# Sheet_20190224.net
KiCad netlist of a schematic drawn in Altium Designer
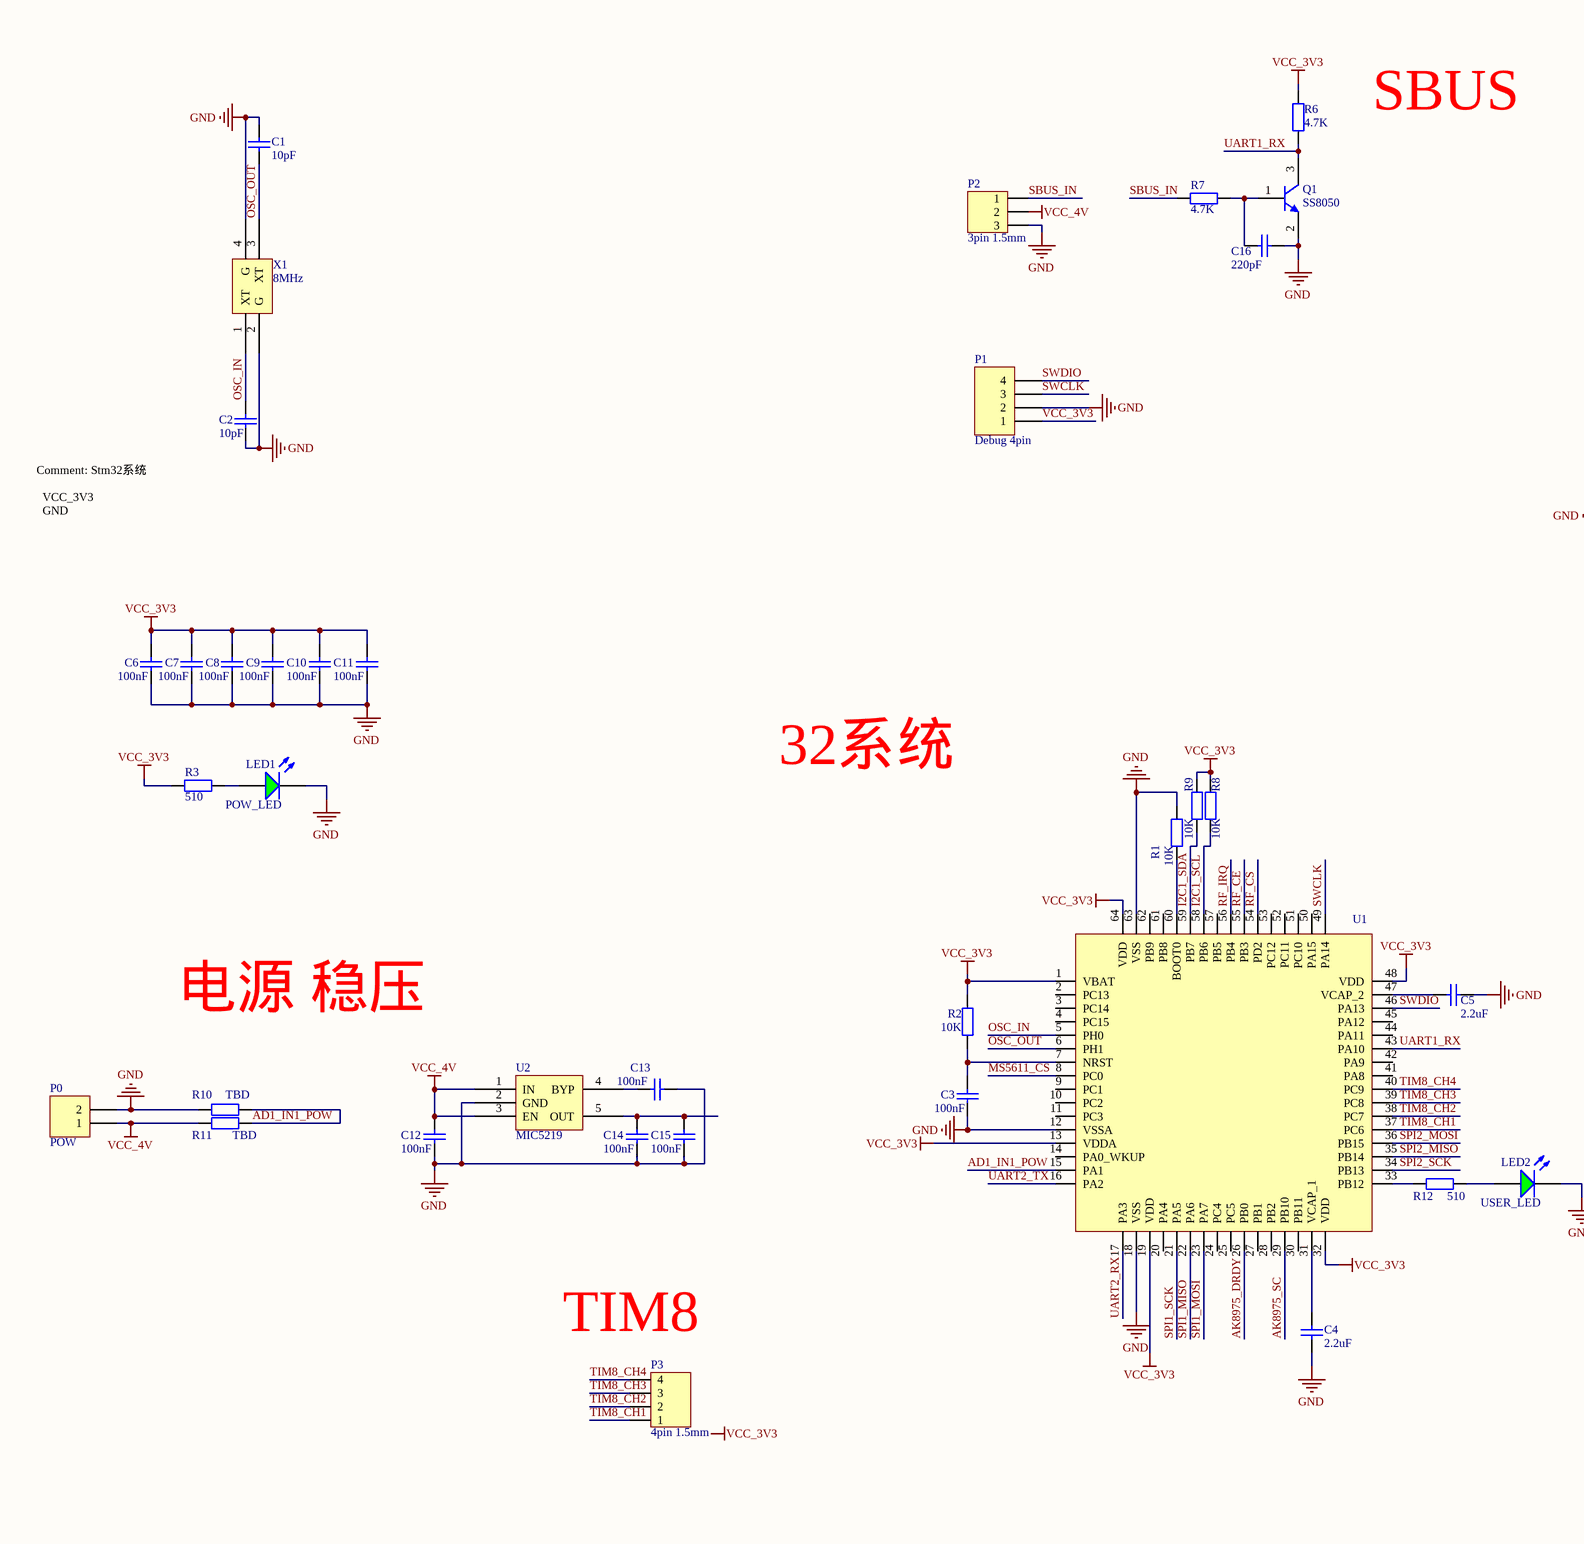
[diagram p0: Sheet_20190224.SchDoc, left]
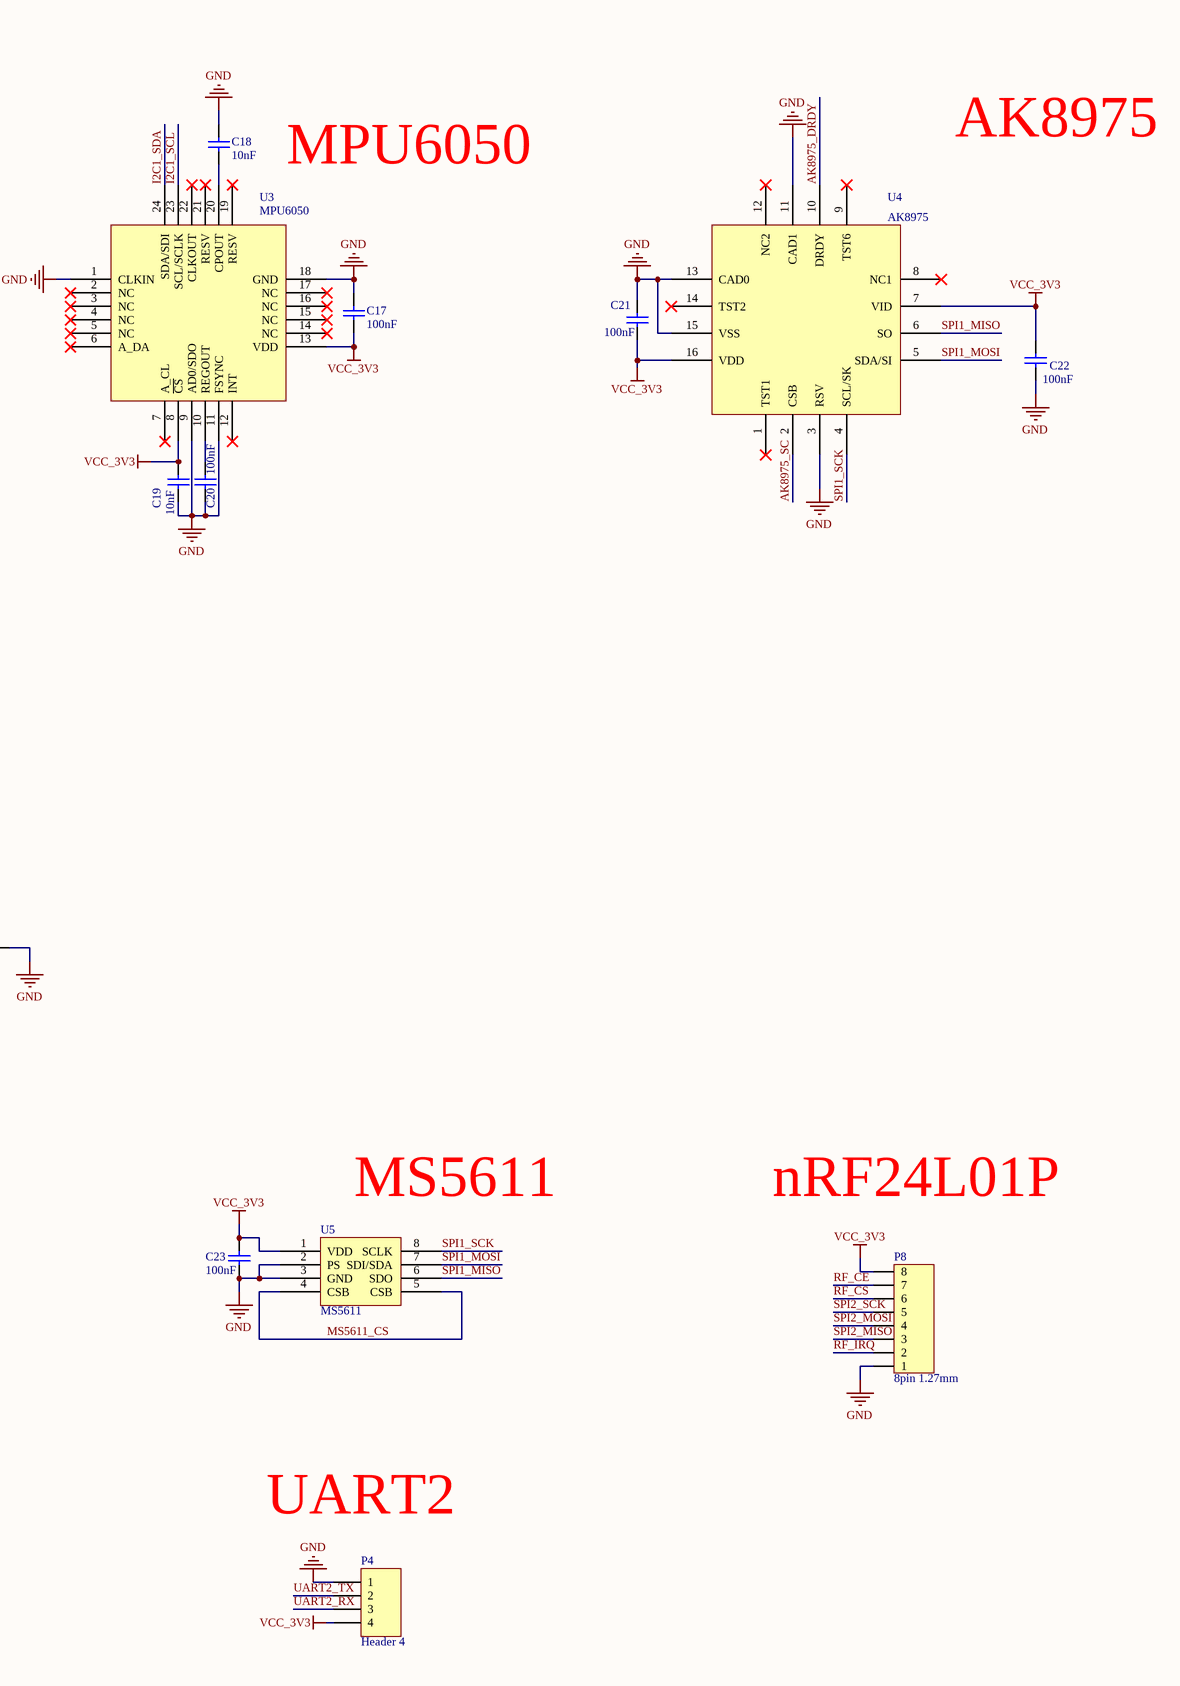
[diagram p1: Sheet_20190224.SchDoc, right]

(export (version "E")
  (design (tool "Eeschema 10.0.6"))
  (components
    (comp (ref "C1")
      (value "10pF")
      (footprint "0402 C")
      (libsource (lib "FlightController_Integrated_Library") (part "0402 C"))
    )
    (comp (ref "C2")
      (value "10pF")
      (footprint "0402 C")
      (libsource (lib "FlightController_Integrated_Library") (part "0402 C"))
    )
    (comp (ref "C3")
      (value "100nF")
      (footprint "0402 C")
      (libsource (lib "FlightController_Integrated_Library") (part "0402 C"))
    )
    (comp (ref "C4")
      (value "2.2uF")
      (footprint "0603 C")
      (libsource (lib "FlightController_Integrated_Library") (part "0603 C"))
    )
    (comp (ref "C5")
      (value "2.2uF")
      (footprint "0603 C")
      (libsource (lib "FlightController_Integrated_Library") (part "0603 C"))
    )
    (comp (ref "C6")
      (value "100nF")
      (footprint "0402 C")
      (libsource (lib "FlightController_Integrated_Library") (part "0402 C"))
    )
    (comp (ref "C7")
      (value "100nF")
      (footprint "0402 C")
      (libsource (lib "FlightController_Integrated_Library") (part "0402 C"))
    )
    (comp (ref "C8")
      (value "100nF")
      (footprint "0402 C")
      (libsource (lib "FlightController_Integrated_Library") (part "0402 C"))
    )
    (comp (ref "C9")
      (value "100nF")
      (footprint "0402 C")
      (libsource (lib "FlightController_Integrated_Library") (part "0402 C"))
    )
    (comp (ref "C10")
      (value "100nF")
      (footprint "0402 C")
      (libsource (lib "FlightController_Integrated_Library") (part "0402 C"))
    )
    (comp (ref "C11")
      (value "100nF")
      (footprint "0402 C")
      (libsource (lib "FlightController_Integrated_Library") (part "0402 C"))
    )
    (comp (ref "C12")
      (value "100nF")
      (footprint "0402 C")
      (libsource (lib "FlightController_Integrated_Library") (part "0402 C"))
    )
    (comp (ref "C13")
      (value "100nF")
      (footprint "0402 C")
      (libsource (lib "FlightController_Integrated_Library") (part "0402 C"))
    )
    (comp (ref "C14")
      (value "100nF")
      (footprint "0402 C")
      (libsource (lib "FlightController_Integrated_Library") (part "0402 C"))
    )
    (comp (ref "C15")
      (value "100nF")
      (footprint "0402 C")
      (libsource (lib "FlightController_Integrated_Library") (part "0402 C"))
    )
    (comp (ref "C16")
      (value "220pF")
      (footprint "0402 C")
      (libsource (lib "FlightController_Integrated_Library") (part "0402 C"))
    )
    (comp (ref "C17")
      (value "100nF")
      (footprint "0402 C")
      (libsource (lib "FlightController_Integrated_Library") (part "0402 C"))
    )
    (comp (ref "C18")
      (value "10nF")
      (footprint "0402 C")
      (libsource (lib "FlightController_Integrated_Library") (part "0402 C"))
    )
    (comp (ref "C19")
      (value "10nF")
      (footprint "0402 C")
      (libsource (lib "FlightController_Integrated_Library") (part "0402 C"))
    )
    (comp (ref "C20")
      (value "100nF")
      (footprint "0402 C")
      (libsource (lib "FlightController_Integrated_Library") (part "0402 C"))
    )
    (comp (ref "C21")
      (value "100nF")
      (footprint "0402 C")
      (libsource (lib "FlightController_Integrated_Library") (part "0402 C"))
    )
    (comp (ref "C22")
      (value "100nF")
      (footprint "0402 C")
      (libsource (lib "FlightController_Integrated_Library") (part "0402 C"))
    )
    (comp (ref "C23")
      (value "100nF")
      (footprint "0402 C")
      (libsource (lib "FlightController_Integrated_Library") (part "0402 C"))
    )
    (comp (ref "LED1")
      (value "POW_LED")
      (footprint "0603 LED")
      (libsource (lib "FlightController_Integrated_Library") (part "0603 LED"))
    )
    (comp (ref "LED2")
      (value "USER_LED")
      (footprint "0603 LED")
      (libsource (lib "FlightController_Integrated_Library") (part "0603 LED"))
    )
    (comp (ref "P0")
      (value "POW")
      (footprint "HDR1X2")
      (description "Header, 2-Pin")
      (fields (field (name "PUBLISHER") "Altium Limited"))
      (libsource (lib "Miscellaneous Connectors") (part "Header 2"))
    )
    (comp (ref "P1")
      (value "Debug 4pin")
      (footprint "GH-1.25 4pin")
      (libsource (lib "FlightController_Integrated_Library") (part "Debug 4pin"))
    )
    (comp (ref "P2")
      (value "3pin 1.5mm")
      (footprint "3pin 1.5mm")
      (libsource (lib "FlightController_Integrated_Library") (part "3pin 1.5mm"))
    )
    (comp (ref "P3")
      (value "4pin 1.5mm")
      (footprint "4pin 1.5mm")
      (libsource (lib "FlightController_Integrated_Library") (part "4pin 1.5mm"))
    )
    (comp (ref "P4")
      (value "Header 4")
      (footprint "HDR1X4")
      (description "Header, 4-Pin")
      (fields (field (name "PUBLISHER") "Altium Limited"))
      (libsource (lib "Miscellaneous Connectors") (part "Header 4"))
    )
    (comp (ref "P8")
      (value "8pin 1.27mm")
      (footprint "8pin 1.27mm")
      (libsource (lib "FlightController_Integrated_Library") (part "8pin 1.27mm"))
    )
    (comp (ref "Q1")
      (value "SS8050")
      (footprint "SOT-23 3pin")
      (libsource (lib "FlightController_Integrated_Library") (part "SS8050"))
    )
    (comp (ref "R1")
      (value "10K")
      (footprint "0402 R")
      (libsource (lib "FlightController_Integrated_Library") (part "0402 R"))
    )
    (comp (ref "R2")
      (value "10K")
      (footprint "0402 R")
      (libsource (lib "FlightController_Integrated_Library") (part "0402 R"))
    )
    (comp (ref "R3") (value "510") (footprint "0402 R") (libsource (lib "") (part "0402 R_3")))
    (comp (ref "R6") (value "4.7K") (footprint "0402 R") (libsource (lib "") (part "0402 R_2")))
    (comp (ref "R7") (value "4.7K") (footprint "0402 R") (libsource (lib "") (part "0402 R_3")))
    (comp (ref "R8") (value "10K") (footprint "0402 R") (libsource (lib "") (part "0402 R_2")))
    (comp (ref "R9") (value "10K") (footprint "0402 R") (libsource (lib "") (part "0402 R_2")))
    (comp (ref "R10") (value "TBD") (footprint "0402 R") (libsource (lib "") (part "0402 R_1")))
    (comp (ref "R11") (value "TBD") (footprint "0402 R") (libsource (lib "") (part "0402 R_1")))
    (comp (ref "R12") (value "510") (footprint "0402 R") (libsource (lib "") (part "0402 R_1")))
    (comp (ref "U1")
      (value "STM32F407VET6_64")
      (footprint "LQFP 64pin")
      (libsource (lib "FlightController_Integrated_Library") (part "STM32F407VET6_64"))
    )
    (comp (ref "U2")
      (value "MIC5219")
      (footprint "SOT-23 5pin")
      (libsource (lib "FlightController_Integrated_Library") (part "MIC5219"))
    )
    (comp (ref "U3")
      (value "MPU6050")
      (footprint "QFN 24pin")
      (libsource (lib "FlightController_Integrated_Library") (part "MPU6000/6050"))
    )
    (comp (ref "U4")
      (value "AK8975")
      (footprint "AK8975")
      (libsource (lib "FlightController_Integrated_Library") (part "AK8975"))
    )
    (comp (ref "U5")
      (value "MS5611")
      (footprint "MS5611")
      (libsource (lib "FlightController_Integrated_Library") (part "MS5611"))
    )
    (comp (ref "X1")
      (value "8MHz")
      (footprint "XTAL_3225 4pin")
      (libsource (lib "FlightController_Integrated_Library") (part "XTAL"))
    )
  )
  (nets
    (net (code "1") (name "/AD1_IN1_POW") (class "Default")
      (node (ref "R10") (pin "2") (pinfunction "2_2") (pintype "passive"))
      (node (ref "R11") (pin "2") (pinfunction "2_2") (pintype "passive"))
      (node (ref "U1") (pin "15") (pinfunction "PA1_15") (pintype "passive"))
    )
    (net (code "2") (name "/AK8975_DRDY") (class "Default")
      (node (ref "U1") (pin "26") (pinfunction "PB0_26") (pintype "passive"))
      (node (ref "U4") (pin "10") (pinfunction "DRDY_10") (pintype "passive"))
    )
    (net (code "3") (name "/AK8975_SC") (class "Default")
      (node (ref "U1") (pin "29") (pinfunction "PB10_29") (pintype "passive"))
      (node (ref "U4") (pin "2") (pinfunction "CSB_2") (pintype "passive"))
    )
    (net (code "4") (name "/I2C1_SCL") (class "Default")
      (node (ref "R8") (pin "2") (pinfunction "2_2") (pintype "passive"))
      (node (ref "U1") (pin "58") (pinfunction "PB6_58") (pintype "passive"))
      (node (ref "U3") (pin "23") (pinfunction "SCL/SCLK_23") (pintype "passive"))
    )
    (net (code "5") (name "/I2C1_SDA") (class "Default")
      (node (ref "R9") (pin "2") (pinfunction "2_2") (pintype "passive"))
      (node (ref "U1") (pin "59") (pinfunction "PB7_59") (pintype "passive"))
      (node (ref "U3") (pin "24") (pinfunction "SDA/SDI_24") (pintype "passive"))
    )
    (net (code "6") (name "/MS5611_CS") (class "Default")
      (node (ref "U1") (pin "8") (pinfunction "PC0_8") (pintype "passive"))
      (node (ref "U5") (pin "4") (pinfunction "CSB_4") (pintype "passive"))
      (node (ref "U5") (pin "5") (pinfunction "CSB_5") (pintype "passive"))
    )
    (net (code "7") (name "/OSC_IN") (class "Default")
      (node (ref "C2") (pin "2") (pinfunction "2_2") (pintype "passive"))
      (node (ref "U1") (pin "5") (pinfunction "PH0_5") (pintype "passive"))
      (node (ref "X1") (pin "1") (pinfunction "XT_1") (pintype "passive"))
    )
    (net (code "8") (name "/OSC_OUT") (class "Default")
      (node (ref "C1") (pin "1") (pinfunction "1_1") (pintype "passive"))
      (node (ref "U1") (pin "6") (pinfunction "PH1_6") (pintype "passive"))
      (node (ref "X1") (pin "3") (pinfunction "XT_3") (pintype "passive"))
    )
    (net (code "9") (name "/RF_CE") (class "Default")
      (node (ref "P8") (pin "7") (pinfunction "7_7") (pintype "passive"))
      (node (ref "U1") (pin "55") (pinfunction "PB3_55") (pintype "passive"))
    )
    (net (code "10") (name "/RF_CS") (class "Default")
      (node (ref "P8") (pin "6") (pinfunction "6_6") (pintype "passive"))
      (node (ref "U1") (pin "54") (pinfunction "PD2_54") (pintype "passive"))
    )
    (net (code "11") (name "/RF_IRQ") (class "Default")
      (node (ref "P8") (pin "2") (pinfunction "2_2") (pintype "passive"))
      (node (ref "U1") (pin "56") (pinfunction "PB4_56") (pintype "passive"))
    )
    (net (code "12") (name "/SBUS_IN") (class "Default")
      (node (ref "P2") (pin "1") (pinfunction "1_1") (pintype "passive"))
      (node (ref "R7") (pin "2") (pinfunction "2_2") (pintype "passive"))
    )
    (net (code "13") (name "/SPI1_MISO") (class "Default")
      (node (ref "U1") (pin "22") (pinfunction "PA6_22") (pintype "passive"))
      (node (ref "U4") (pin "6") (pinfunction "SO_6") (pintype "passive"))
      (node (ref "U5") (pin "6") (pinfunction "SDO_6") (pintype "passive"))
    )
    (net (code "14") (name "/SPI1_MOSI") (class "Default")
      (node (ref "U1") (pin "23") (pinfunction "PA7_23") (pintype "passive"))
      (node (ref "U4") (pin "5") (pinfunction "SDA/SI_5") (pintype "passive"))
      (node (ref "U5") (pin "7") (pinfunction "SDI/SDA_7") (pintype "passive"))
    )
    (net (code "15") (name "/SPI1_SCK") (class "Default")
      (node (ref "U1") (pin "21") (pinfunction "PA5_21") (pintype "passive"))
      (node (ref "U4") (pin "4") (pinfunction "SCL/SK_4") (pintype "passive"))
      (node (ref "U5") (pin "8") (pinfunction "SCLK_8") (pintype "passive"))
    )
    (net (code "16") (name "/SPI2_MISO") (class "Default")
      (node (ref "P8") (pin "3") (pinfunction "3_3") (pintype "passive"))
      (node (ref "U1") (pin "35") (pinfunction "PB14_35") (pintype "passive"))
    )
    (net (code "17") (name "/SPI2_MOSI") (class "Default")
      (node (ref "P8") (pin "4") (pinfunction "4_4") (pintype "passive"))
      (node (ref "U1") (pin "36") (pinfunction "PB15_36") (pintype "passive"))
    )
    (net (code "18") (name "/SPI2_SCK") (class "Default")
      (node (ref "P8") (pin "5") (pinfunction "5_5") (pintype "passive"))
      (node (ref "U1") (pin "34") (pinfunction "PB13_34") (pintype "passive"))
    )
    (net (code "19") (name "/SWCLK") (class "Default")
      (node (ref "P1") (pin "3") (pinfunction "3_3") (pintype "passive"))
      (node (ref "U1") (pin "49") (pinfunction "PA14_49") (pintype "passive"))
    )
    (net (code "20") (name "/SWDIO") (class "Default")
      (node (ref "P1") (pin "4") (pinfunction "4_4") (pintype "passive"))
      (node (ref "U1") (pin "46") (pinfunction "PA13_46") (pintype "passive"))
    )
    (net (code "21") (name "/TIM8_CH1") (class "Default")
      (node (ref "P3") (pin "1") (pinfunction "1_1") (pintype "passive"))
      (node (ref "U1") (pin "37") (pinfunction "PC6_37") (pintype "passive"))
    )
    (net (code "22") (name "/TIM8_CH2") (class "Default")
      (node (ref "P3") (pin "2") (pinfunction "2_2") (pintype "passive"))
      (node (ref "U1") (pin "38") (pinfunction "PC7_38") (pintype "passive"))
    )
    (net (code "23") (name "/TIM8_CH3") (class "Default")
      (node (ref "P3") (pin "3") (pinfunction "3_3") (pintype "passive"))
      (node (ref "U1") (pin "39") (pinfunction "PC8_39") (pintype "passive"))
    )
    (net (code "24") (name "/TIM8_CH4") (class "Default")
      (node (ref "P3") (pin "4") (pinfunction "4_4") (pintype "passive"))
      (node (ref "U1") (pin "40") (pinfunction "PC9_40") (pintype "passive"))
    )
    (net (code "25") (name "/UART1_RX") (class "Default")
      (node (ref "Q1") (pin "3") (pinfunction "C_3") (pintype "passive"))
      (node (ref "R6") (pin "2") (pinfunction "2_2") (pintype "passive"))
      (node (ref "U1") (pin "43") (pinfunction "PA10_43") (pintype "passive"))
    )
    (net (code "26") (name "/UART2_RX") (class "Default")
      (node (ref "P4") (pin "3") (pinfunction "3_3") (pintype "passive"))
      (node (ref "U1") (pin "17") (pinfunction "PA3_17") (pintype "passive"))
    )
    (net (code "27") (name "/UART2_TX") (class "Default")
      (node (ref "P4") (pin "2") (pinfunction "2_2") (pintype "passive"))
      (node (ref "U1") (pin "16") (pinfunction "PA2_16") (pintype "passive"))
    )
    (net (code "28") (name "GND") (class "Default")
      (node (ref "C1") (pin "2") (pinfunction "2_2") (pintype "passive"))
      (node (ref "C10") (pin "1") (pinfunction "1_1") (pintype "passive"))
      (node (ref "C11") (pin "1") (pinfunction "1_1") (pintype "passive"))
      (node (ref "C12") (pin "1") (pinfunction "1_1") (pintype "passive"))
      (node (ref "C13") (pin "1") (pinfunction "1_1") (pintype "passive"))
      (node (ref "C14") (pin "1") (pinfunction "1_1") (pintype "passive"))
      (node (ref "C15") (pin "1") (pinfunction "1_1") (pintype "passive"))
      (node (ref "C16") (pin "1") (pinfunction "1_1") (pintype "passive"))
      (node (ref "C17") (pin "1") (pinfunction "1_1") (pintype "passive"))
      (node (ref "C18") (pin "1") (pinfunction "1_1") (pintype "passive"))
      (node (ref "C19") (pin "2") (pinfunction "2_2") (pintype "passive"))
      (node (ref "C2") (pin "1") (pinfunction "1_1") (pintype "passive"))
      (node (ref "C20") (pin "2") (pinfunction "2_2") (pintype "passive"))
      (node (ref "C21") (pin "1") (pinfunction "1_1") (pintype "passive"))
      (node (ref "C22") (pin "2") (pinfunction "2_2") (pintype "passive"))
      (node (ref "C23") (pin "1") (pinfunction "1_1") (pintype "passive"))
      (node (ref "C3") (pin "1") (pinfunction "1_1") (pintype "passive"))
      (node (ref "C4") (pin "1") (pinfunction "1_1") (pintype "passive"))
      (node (ref "C5") (pin "1") (pinfunction "1_1") (pintype "passive"))
      (node (ref "C6") (pin "1") (pinfunction "1_1") (pintype "passive"))
      (node (ref "C7") (pin "1") (pinfunction "1_1") (pintype "passive"))
      (node (ref "C8") (pin "1") (pinfunction "1_1") (pintype "passive"))
      (node (ref "C9") (pin "1") (pinfunction "1_1") (pintype "passive"))
      (node (ref "LED1") (pin "K") (pinfunction "K_K") (pintype "passive"))
      (node (ref "LED2") (pin "K") (pinfunction "K_K") (pintype "passive"))
      (node (ref "P0") (pin "2") (pinfunction "2_2") (pintype "passive"))
      (node (ref "P1") (pin "2") (pinfunction "2_2") (pintype "passive"))
      (node (ref "P2") (pin "3") (pinfunction "3_3") (pintype "passive"))
      (node (ref "P4") (pin "1") (pinfunction "1_1") (pintype "passive"))
      (node (ref "P8") (pin "1") (pinfunction "1_1") (pintype "passive"))
      (node (ref "Q1") (pin "2") (pinfunction "E_2") (pintype "passive"))
      (node (ref "R1") (pin "2") (pinfunction "2_2") (pintype "passive"))
      (node (ref "R10") (pin "1") (pinfunction "1_1") (pintype "passive"))
      (node (ref "U1") (pin "12") (pinfunction "VSSA_12") (pintype "passive"))
      (node (ref "U1") (pin "18") (pinfunction "VSS_18") (pintype "passive"))
      (node (ref "U1") (pin "63") (pinfunction "VSS_63") (pintype "passive"))
      (node (ref "U2") (pin "2") (pinfunction "GND_2") (pintype "passive"))
      (node (ref "U3") (pin "1") (pinfunction "CLKIN_1") (pintype "passive"))
      (node (ref "U3") (pin "11") (pinfunction "FSYNC_11") (pintype "passive"))
      (node (ref "U3") (pin "18") (pinfunction "GND_18") (pintype "passive"))
      (node (ref "U3") (pin "9") (pinfunction "AD0/SDO_9") (pintype "passive"))
      (node (ref "U4") (pin "11") (pinfunction "CAD1_11") (pintype "passive"))
      (node (ref "U4") (pin "13") (pinfunction "CAD0_13") (pintype "passive"))
      (node (ref "U4") (pin "15") (pinfunction "VSS_15") (pintype "passive"))
      (node (ref "U4") (pin "3") (pinfunction "RSV_3") (pintype "passive"))
      (node (ref "U5") (pin "2") (pinfunction "PS_2") (pintype "passive"))
      (node (ref "U5") (pin "3") (pinfunction "GND_3") (pintype "passive"))
      (node (ref "X1") (pin "2") (pinfunction "G_2") (pintype "passive"))
      (node (ref "X1") (pin "4") (pinfunction "G_4") (pintype "passive"))
    )
    (net (code "29") (name "Net-(LED1-PadA)") (class "Default")
      (node (ref "LED1") (pin "A") (pinfunction "A_A") (pintype "passive"))
      (node (ref "R3") (pin "1") (pinfunction "1_1") (pintype "passive"))
    )
    (net (code "30") (name "Net-(LED2-PadA)") (class "Default")
      (node (ref "LED2") (pin "A") (pinfunction "A_A") (pintype "passive"))
      (node (ref "R12") (pin "2") (pinfunction "2_2") (pintype "passive"))
    )
    (net (code "31") (name "Net-(Q1-B)") (class "Default")
      (node (ref "C16") (pin "2") (pinfunction "2_2") (pintype "passive"))
      (node (ref "Q1") (pin "1") (pinfunction "B_1") (pintype "passive"))
      (node (ref "R7") (pin "1") (pinfunction "1_1") (pintype "passive"))
    )
    (net (code "32") (name "Net-(U1-BOOT0)") (class "Default")
      (node (ref "R1") (pin "1") (pinfunction "1_1") (pintype "passive"))
      (node (ref "U1") (pin "60") (pinfunction "BOOT0_60") (pintype "passive"))
    )
    (net (code "33") (name "Net-(U1-NRST)") (class "Default")
      (node (ref "C3") (pin "2") (pinfunction "2_2") (pintype "passive"))
      (node (ref "R2") (pin "1") (pinfunction "1_1") (pintype "passive"))
      (node (ref "U1") (pin "7") (pinfunction "NRST_7") (pintype "passive"))
    )
    (net (code "34") (name "Net-(U1-PB12)") (class "Default")
      (node (ref "R12") (pin "1") (pinfunction "1_1") (pintype "passive"))
      (node (ref "U1") (pin "33") (pinfunction "PB12_33") (pintype "passive"))
    )
    (net (code "35") (name "Net-(U1-VCAP_1)") (class "Default")
      (node (ref "C4") (pin "2") (pinfunction "2_2") (pintype "passive"))
      (node (ref "U1") (pin "31") (pinfunction "VCAP_1_31") (pintype "passive"))
    )
    (net (code "36") (name "Net-(U1-VCAP_2)") (class "Default")
      (node (ref "C5") (pin "2") (pinfunction "2_2") (pintype "passive"))
      (node (ref "U1") (pin "47") (pinfunction "VCAP_2_47") (pintype "passive"))
    )
    (net (code "37") (name "Net-(U2-BYP)") (class "Default")
      (node (ref "C13") (pin "2") (pinfunction "2_2") (pintype "passive"))
      (node (ref "U2") (pin "4") (pinfunction "BYP_4") (pintype "passive"))
    )
    (net (code "38") (name "Net-(U2-OUT)") (class "Default")
      (node (ref "C14") (pin "2") (pinfunction "2_2") (pintype "passive"))
      (node (ref "C15") (pin "2") (pinfunction "2_2") (pintype "passive"))
      (node (ref "U2") (pin "5") (pinfunction "OUT_5") (pintype "passive"))
    )
    (net (code "39") (name "Net-(U3-CPOUT)") (class "Default")
      (node (ref "C18") (pin "2") (pinfunction "2_2") (pintype "passive"))
      (node (ref "U3") (pin "20") (pinfunction "CPOUT_20") (pintype "passive"))
    )
    (net (code "40") (name "Net-(U3-REGOUT)") (class "Default")
      (node (ref "C20") (pin "1") (pinfunction "1_1") (pintype "passive"))
      (node (ref "U3") (pin "10") (pinfunction "REGOUT_10") (pintype "passive"))
    )
    (net (code "41") (name "VCC_3V3") (class "Default")
      (node (ref "C10") (pin "2") (pinfunction "2_2") (pintype "passive"))
      (node (ref "C11") (pin "2") (pinfunction "2_2") (pintype "passive"))
      (node (ref "C17") (pin "2") (pinfunction "2_2") (pintype "passive"))
      (node (ref "C19") (pin "1") (pinfunction "1_1") (pintype "passive"))
      (node (ref "C21") (pin "2") (pinfunction "2_2") (pintype "passive"))
      (node (ref "C22") (pin "1") (pinfunction "1_1") (pintype "passive"))
      (node (ref "C23") (pin "2") (pinfunction "2_2") (pintype "passive"))
      (node (ref "C6") (pin "2") (pinfunction "2_2") (pintype "passive"))
      (node (ref "C7") (pin "2") (pinfunction "2_2") (pintype "passive"))
      (node (ref "C8") (pin "2") (pinfunction "2_2") (pintype "passive"))
      (node (ref "C9") (pin "2") (pinfunction "2_2") (pintype "passive"))
      (node (ref "P1") (pin "1") (pinfunction "1_1") (pintype "passive"))
      (node (ref "P4") (pin "4") (pinfunction "4_4") (pintype "passive"))
      (node (ref "P8") (pin "8") (pinfunction "8_8") (pintype "passive"))
      (node (ref "R2") (pin "2") (pinfunction "2_2") (pintype "passive"))
      (node (ref "R3") (pin "2") (pinfunction "2_2") (pintype "passive"))
      (node (ref "R6") (pin "1") (pinfunction "1_1") (pintype "passive"))
      (node (ref "R8") (pin "1") (pinfunction "1_1") (pintype "passive"))
      (node (ref "R9") (pin "1") (pinfunction "1_1") (pintype "passive"))
      (node (ref "U1") (pin "1") (pinfunction "VBAT_1") (pintype "passive"))
      (node (ref "U1") (pin "13") (pinfunction "VDDA_13") (pintype "passive"))
      (node (ref "U1") (pin "19") (pinfunction "VDD_19") (pintype "passive"))
      (node (ref "U1") (pin "32") (pinfunction "VDD_32") (pintype "passive"))
      (node (ref "U1") (pin "48") (pinfunction "VDD_48") (pintype "passive"))
      (node (ref "U1") (pin "64") (pinfunction "VDD_64") (pintype "passive"))
      (node (ref "U3") (pin "13") (pinfunction "VDD_13") (pintype "passive"))
      (node (ref "U3") (pin "8") (pinfunction "~{CS}_8") (pintype "passive"))
      (node (ref "U4") (pin "16") (pinfunction "VDD_16") (pintype "passive"))
      (node (ref "U4") (pin "7") (pinfunction "VID_7") (pintype "passive"))
      (node (ref "U5") (pin "1") (pinfunction "VDD_1") (pintype "passive"))
    )
    (net (code "42") (name "VCC_4V") (class "Default")
      (node (ref "C12") (pin "2") (pinfunction "2_2") (pintype "passive"))
      (node (ref "P0") (pin "1") (pinfunction "1_1") (pintype "passive"))
      (node (ref "P2") (pin "2") (pinfunction "2_2") (pintype "passive"))
      (node (ref "R11") (pin "1") (pinfunction "1_1") (pintype "passive"))
      (node (ref "U2") (pin "1") (pinfunction "IN_1") (pintype "passive"))
      (node (ref "U2") (pin "3") (pinfunction "EN_3") (pintype "passive"))
    )
    (net (code "43") (name "unconnected-(U1-PA0_WKUP-Pad14)") (class "Default")
      (node (ref "U1") (pin "14") (pinfunction "PA0_WKUP_14") (pintype "passive"))
    )
    (net (code "44") (name "unconnected-(U1-PA4-Pad20)") (class "Default")
      (node (ref "U1") (pin "20") (pinfunction "PA4_20") (pintype "passive"))
    )
    (net (code "45") (name "unconnected-(U1-PA8-Pad41)") (class "Default")
      (node (ref "U1") (pin "41") (pinfunction "PA8_41") (pintype "passive"))
    )
    (net (code "46") (name "unconnected-(U1-PA9-Pad42)") (class "Default")
      (node (ref "U1") (pin "42") (pinfunction "PA9_42") (pintype "passive"))
    )
    (net (code "47") (name "unconnected-(U1-PA11-Pad44)") (class "Default")
      (node (ref "U1") (pin "44") (pinfunction "PA11_44") (pintype "passive"))
    )
    (net (code "48") (name "unconnected-(U1-PA12-Pad45)") (class "Default")
      (node (ref "U1") (pin "45") (pinfunction "PA12_45") (pintype "passive"))
    )
    (net (code "49") (name "unconnected-(U1-PA15-Pad50)") (class "Default")
      (node (ref "U1") (pin "50") (pinfunction "PA15_50") (pintype "passive"))
    )
    (net (code "50") (name "unconnected-(U1-PB1-Pad27)") (class "Default")
      (node (ref "U1") (pin "27") (pinfunction "PB1_27") (pintype "passive"))
    )
    (net (code "51") (name "unconnected-(U1-PB2-Pad28)") (class "Default")
      (node (ref "U1") (pin "28") (pinfunction "PB2_28") (pintype "passive"))
    )
    (net (code "52") (name "unconnected-(U1-PB5-Pad57)") (class "Default")
      (node (ref "U1") (pin "57") (pinfunction "PB5_57") (pintype "passive"))
    )
    (net (code "53") (name "unconnected-(U1-PB8-Pad61)") (class "Default")
      (node (ref "U1") (pin "61") (pinfunction "PB8_61") (pintype "passive"))
    )
    (net (code "54") (name "unconnected-(U1-PB9-Pad62)") (class "Default")
      (node (ref "U1") (pin "62") (pinfunction "PB9_62") (pintype "passive"))
    )
    (net (code "55") (name "unconnected-(U1-PB11-Pad30)") (class "Default")
      (node (ref "U1") (pin "30") (pinfunction "PB11_30") (pintype "passive"))
    )
    (net (code "56") (name "unconnected-(U1-PC1-Pad9)") (class "Default")
      (node (ref "U1") (pin "9") (pinfunction "PC1_9") (pintype "passive"))
    )
    (net (code "57") (name "unconnected-(U1-PC2-Pad10)") (class "Default")
      (node (ref "U1") (pin "10") (pinfunction "PC2_10") (pintype "passive"))
    )
    (net (code "58") (name "unconnected-(U1-PC3-Pad11)") (class "Default")
      (node (ref "U1") (pin "11") (pinfunction "PC3_11") (pintype "passive"))
    )
    (net (code "59") (name "unconnected-(U1-PC4-Pad24)") (class "Default")
      (node (ref "U1") (pin "24") (pinfunction "PC4_24") (pintype "passive"))
    )
    (net (code "60") (name "unconnected-(U1-PC5-Pad25)") (class "Default")
      (node (ref "U1") (pin "25") (pinfunction "PC5_25") (pintype "passive"))
    )
    (net (code "61") (name "unconnected-(U1-PC10-Pad51)") (class "Default")
      (node (ref "U1") (pin "51") (pinfunction "PC10_51") (pintype "passive"))
    )
    (net (code "62") (name "unconnected-(U1-PC11-Pad52)") (class "Default")
      (node (ref "U1") (pin "52") (pinfunction "PC11_52") (pintype "passive"))
    )
    (net (code "63") (name "unconnected-(U1-PC12-Pad53)") (class "Default")
      (node (ref "U1") (pin "53") (pinfunction "PC12_53") (pintype "passive"))
    )
    (net (code "64") (name "unconnected-(U1-PC13-Pad2)") (class "Default")
      (node (ref "U1") (pin "2") (pinfunction "PC13_2") (pintype "passive"))
    )
    (net (code "65") (name "unconnected-(U1-PC14-Pad3)") (class "Default")
      (node (ref "U1") (pin "3") (pinfunction "PC14_3") (pintype "passive"))
    )
    (net (code "66") (name "unconnected-(U1-PC15-Pad4)") (class "Default")
      (node (ref "U1") (pin "4") (pinfunction "PC15_4") (pintype "passive"))
    )
    (net (code "67") (name "unconnected-(U3-A_CL-Pad7)") (class "Default")
      (node (ref "U3") (pin "7") (pinfunction "A_CL_7") (pintype "passive+no_connect"))
    )
    (net (code "68") (name "unconnected-(U3-A_DA-Pad6)") (class "Default")
      (node (ref "U3") (pin "6") (pinfunction "A_DA_6") (pintype "passive+no_connect"))
    )
    (net (code "69") (name "unconnected-(U3-CLKOUT-Pad22)") (class "Default")
      (node (ref "U3") (pin "22") (pinfunction "CLKOUT_22") (pintype "passive+no_connect"))
    )
    (net (code "70") (name "unconnected-(U3-INT-Pad12)") (class "Default")
      (node (ref "U3") (pin "12") (pinfunction "INT_12") (pintype "passive+no_connect"))
    )
    (net (code "71") (name "unconnected-(U3-NC-Pad2)") (class "Default")
      (node (ref "U3") (pin "2") (pinfunction "NC_2") (pintype "passive+no_connect"))
    )
    (net (code "72") (name "unconnected-(U3-NC-Pad3)") (class "Default")
      (node (ref "U3") (pin "3") (pinfunction "NC_3") (pintype "passive+no_connect"))
    )
    (net (code "73") (name "unconnected-(U3-NC-Pad4)") (class "Default")
      (node (ref "U3") (pin "4") (pinfunction "NC_4") (pintype "passive+no_connect"))
    )
    (net (code "74") (name "unconnected-(U3-NC-Pad5)") (class "Default")
      (node (ref "U3") (pin "5") (pinfunction "NC_5") (pintype "passive+no_connect"))
    )
    (net (code "75") (name "unconnected-(U3-NC-Pad14)") (class "Default")
      (node (ref "U3") (pin "14") (pinfunction "NC_14") (pintype "passive+no_connect"))
    )
    (net (code "76") (name "unconnected-(U3-NC-Pad15)") (class "Default")
      (node (ref "U3") (pin "15") (pinfunction "NC_15") (pintype "passive+no_connect"))
    )
    (net (code "77") (name "unconnected-(U3-NC-Pad16)") (class "Default")
      (node (ref "U3") (pin "16") (pinfunction "NC_16") (pintype "passive+no_connect"))
    )
    (net (code "78") (name "unconnected-(U3-NC-Pad17)") (class "Default")
      (node (ref "U3") (pin "17") (pinfunction "NC_17") (pintype "passive+no_connect"))
    )
    (net (code "79") (name "unconnected-(U3-RESV-Pad19)") (class "Default")
      (node (ref "U3") (pin "19") (pinfunction "RESV_19") (pintype "passive+no_connect"))
    )
    (net (code "80") (name "unconnected-(U3-RESV-Pad21)") (class "Default")
      (node (ref "U3") (pin "21") (pinfunction "RESV_21") (pintype "passive+no_connect"))
    )
    (net (code "81") (name "unconnected-(U4-NC1-Pad8)") (class "Default")
      (node (ref "U4") (pin "8") (pinfunction "NC1_8") (pintype "passive+no_connect"))
    )
    (net (code "82") (name "unconnected-(U4-NC2-Pad12)") (class "Default")
      (node (ref "U4") (pin "12") (pinfunction "NC2_12") (pintype "passive+no_connect"))
    )
    (net (code "83") (name "unconnected-(U4-TST1-Pad1)") (class "Default")
      (node (ref "U4") (pin "1") (pinfunction "TST1_1") (pintype "passive+no_connect"))
    )
    (net (code "84") (name "unconnected-(U4-TST2-Pad14)") (class "Default")
      (node (ref "U4") (pin "14") (pinfunction "TST2_14") (pintype "passive+no_connect"))
    )
    (net (code "85") (name "unconnected-(U4-TST6-Pad9)") (class "Default")
      (node (ref "U4") (pin "9") (pinfunction "TST6_9") (pintype "passive+no_connect"))
    )
  )
)
